# main06kaikai.net
KiCad netlist of a schematic drawn in EAGLE
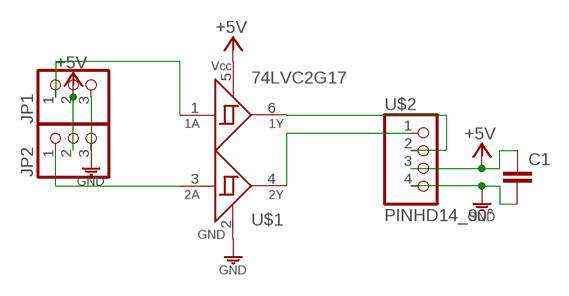
[diagram p0: schematic, sheet 1]

(export (version "E")
  (design (tool "Eeschema 10.0.6"))
  (components
    (comp (ref "C1")
      (value "MLCC-2")
      (footprint "eagle-import:MLCC_25")
      (libsource (lib "eagle-import") (part "MLCC-2"))
    )
    (comp (ref "JP1")
      (value "PINHD-13_90°")
      (footprint "eagle-import:1_3_90")
      (libsource (lib "eagle-import") (part "PINHD-13_90°"))
    )
    (comp (ref "JP2")
      (value "PINHD-13_90°")
      (footprint "eagle-import:1_3_90")
      (libsource (lib "eagle-import") (part "PINHD-13_90°"))
    )
    (comp (ref "U$1")
      (value "74LVC2G17")
      (footprint "eagle-import:74LVC2G17")
      (libsource (lib "eagle-import") (part "74LVC2G17"))
    )
    (comp (ref "U$2")
      (value "PINHD14_90°")
      (footprint "eagle-import:1_4_90")
      (libsource (lib "eagle-import") (part "PINHD14_90°"))
    )
  )
  (nets
    (net (code "1") (name "+5V") (class "Default")
      (node (ref "C1") (pin "1") (pinfunction "1_1") (pintype "passive"))
      (node (ref "JP1") (pin "2") (pinfunction "2_2") (pintype "passive"))
      (node (ref "JP2") (pin "2") (pinfunction "2_2") (pintype "passive"))
      (node (ref "U$1") (pin "5") (pinfunction "5_5") (pintype "bidirectional"))
      (node (ref "U$2") (pin "3") (pinfunction "3_3") (pintype "passive"))
    )
    (net (code "2") (name "GND") (class "Default")
      (node (ref "C1") (pin "2") (pinfunction "2_2") (pintype "passive"))
      (node (ref "JP1") (pin "3") (pinfunction "3_3") (pintype "passive"))
      (node (ref "JP2") (pin "3") (pinfunction "3_3") (pintype "passive"))
      (node (ref "U$1") (pin "2") (pinfunction "2_2") (pintype "bidirectional"))
      (node (ref "U$2") (pin "4") (pinfunction "4_4") (pintype "passive"))
    )
    (net (code "3") (name "Net-(JP1-Pad1)") (class "Default")
      (node (ref "JP1") (pin "1") (pinfunction "1_1") (pintype "passive"))
      (node (ref "U$1") (pin "1") (pinfunction "1_1") (pintype "bidirectional"))
    )
    (net (code "4") (name "Net-(JP2-Pad1)") (class "Default")
      (node (ref "JP2") (pin "1") (pinfunction "1_1") (pintype "passive"))
      (node (ref "U$1") (pin "3") (pinfunction "3_3") (pintype "bidirectional"))
    )
    (net (code "5") (name "Net-(U$1-Pad4)") (class "Default")
      (node (ref "U$1") (pin "4") (pinfunction "4_4") (pintype "bidirectional"))
      (node (ref "U$2") (pin "1") (pinfunction "1_1") (pintype "passive"))
    )
    (net (code "6") (name "Net-(U$1-Pad6)") (class "Default")
      (node (ref "U$1") (pin "6") (pinfunction "6_6") (pintype "bidirectional"))
      (node (ref "U$2") (pin "2") (pinfunction "2_2") (pintype "passive"))
    )
  )
)
